# HLib-SPIDevices.net
KiCad netlist of a schematic drawn in Altium Designer
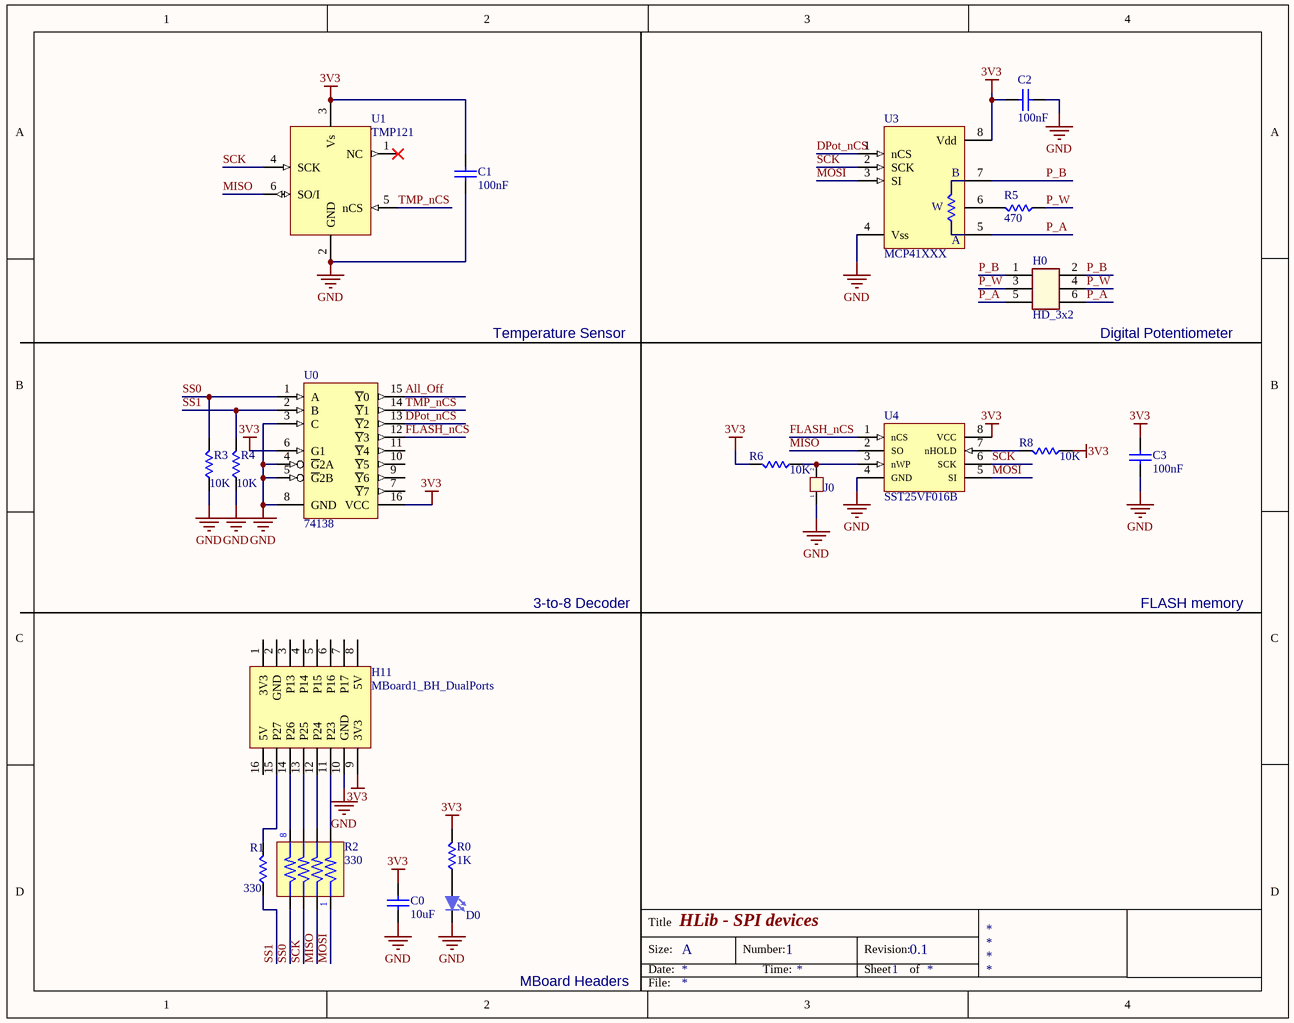
[diagram p0: HLib-SPIDevices.SchDoc]

(export (version "E")
  (design (tool "Eeschema 10.0.6"))
  (components
    (comp (ref "C0")
      (value "10uF")
      (footprint "SM_0805_C_CERAMIC")
      (description "Non-polarity ceramic capacitor")
      (fields (field (name "Comment") "C_Ceramic") (field (name "PUBLISHER") "Altium Limited"))
      (libsource (lib "HLib_discrete_sch") (part "C_Ceramic"))
    )
    (comp (ref "C1")
      (value "100nF")
      (footprint "SM_0805_C_CERAMIC")
      (description "Non-polarity ceramic capacitor")
      (fields (field (name "Comment") "C_Ceramic") (field (name "PUBLISHER") "Altium Limited"))
      (libsource (lib "HLib_discrete_sch") (part "C_Ceramic"))
    )
    (comp (ref "C2")
      (value "100nF")
      (footprint "SM_0805_C_CERAMIC")
      (description "Non-polarity ceramic capacitor")
      (fields (field (name "Comment") "C_Ceramic") (field (name "PUBLISHER") "Altium Limited"))
      (libsource (lib "HLib_discrete_sch") (part "C_Ceramic"))
    )
    (comp (ref "C3")
      (value "100nF")
      (footprint "SM_0805_C_CERAMIC")
      (description "Non-polarity ceramic capacitor")
      (fields (field (name "Comment") "C_Ceramic") (field (name "PUBLISHER") "Altium Limited"))
      (libsource (lib "HLib_discrete_sch") (part "C_Ceramic"))
    )
    (comp (ref "D0")
      (value "LED")
      (footprint "SM_0805_LED")
      (fields (field (name "PUBLISHER") "Altium Limited"))
      (libsource (lib "HLib_discrete_sch") (part "LED"))
    )
    (comp (ref "H0")
      (value "HD_3x2")
      (footprint "HD_male_3x2_100mil_straight")
      (description "Header, 3-pins/row, double row,")
      (libsource (lib "HLib_connector_sch") (part "HD_3x2"))
    )
    (comp (ref "H11")
      (value "MBoard1_BH_DualPorts")
      (footprint "MBoard1_BH_DualPorts")
      (libsource (lib "Nhat_Lib") (part "MBoard1_BH_DualPorts"))
    )
    (comp (ref "J0")
      (value "Jumper 2")
      (footprint "HD_MALE_2_100mil_straight")
      (libsource (lib "VioletofSun") (part "JP 2"))
    )
    (comp (ref "R0")
      (value "1K")
      (footprint "SM_0805_R")
      (description "Resistor")
      (fields (field (name "Comment") "R") (field (name "PUBLISHER") "Altium Limited"))
      (libsource (lib "HLib_discrete_sch") (part "R"))
    )
    (comp (ref "R1")
      (value "330")
      (footprint "SM_0805_R")
      (description "Resistor")
      (fields (field (name "Comment") "R") (field (name "PUBLISHER") "Altium Limited"))
      (libsource (lib "HLib_discrete_sch") (part "R"))
    )
    (comp (ref "R2") (value "330") (footprint "RA4") (libsource (lib "Nhat_Lib") (part "RA4")))
    (comp (ref "R3")
      (value "10K")
      (footprint "SM_0805_R")
      (description "Resistor")
      (fields (field (name "Comment") "R") (field (name "PUBLISHER") "Altium Limited"))
      (libsource (lib "HLib_discrete_sch") (part "R"))
    )
    (comp (ref "R4")
      (value "10K")
      (footprint "SM_0805_R")
      (description "Resistor")
      (fields (field (name "Comment") "R") (field (name "PUBLISHER") "Altium Limited"))
      (libsource (lib "HLib_discrete_sch") (part "R"))
    )
    (comp (ref "R5")
      (value "470")
      (footprint "SM_0805_R")
      (description "Resistor")
      (fields (field (name "PUBLISHER") "Altium Limited"))
      (libsource (lib "HLib_discrete_sch") (part "R"))
    )
    (comp (ref "R6")
      (value "10K")
      (footprint "SM_0805_R")
      (description "Resistor")
      (fields (field (name "PUBLISHER") "Altium Limited"))
      (libsource (lib "HLib_discrete_sch") (part "R"))
    )
    (comp (ref "R8")
      (value "10K")
      (footprint "SM_0805_R")
      (description "Resistor")
      (fields (field (name "PUBLISHER") "Altium Limited"))
      (libsource (lib "HLib_discrete_sch") (part "R"))
    )
    (comp (ref "U0")
      (value "74138")
      (footprint "SO-16")
      (description "3 -to- 8 Decoder - Out Low")
      (fields (field (name "COPYRIGHT BY") "VanDungEvn@Gmail.com"))
      (libsource (lib "Nhat_Lib") (part "74138"))
    )
    (comp (ref "U1") (value "TMP121") (footprint "SC70-6") (libsource (lib "Nhat_Lib") (part "TMP121")))
    (comp (ref "U3") (value "MCP41XXX") (footprint "SO-8") (libsource (lib "Nhat_Lib") (part "MCP41XXX")))
    (comp (ref "U4")
      (value "SST25VF016B")
      (footprint "SO-8")
      (libsource (lib "Nhat_Lib") (part "SST25VF016B"))
    )
  )
  (nets
    (net (code "1") (name "/All_Off") (class "Default")
      (node (ref "U0") (pin "15") (pinfunction "~{Y}0_15") (pintype "output"))
    )
    (net (code "2") (name "/DPot_nCS") (class "Default")
      (node (ref "U0") (pin "13") (pinfunction "~{Y}2_13") (pintype "output"))
      (node (ref "U3") (pin "1") (pinfunction "nCS_1") (pintype "input"))
    )
    (net (code "3") (name "/FLASH_nCS") (class "Default")
      (node (ref "U0") (pin "12") (pinfunction "~{Y}3_12") (pintype "output"))
      (node (ref "U4") (pin "1") (pinfunction "nCS_1") (pintype "input"))
    )
    (net (code "4") (name "/MISO") (class "Default")
      (node (ref "R2") (pin "3") (pinfunction "3_3") (pintype "passive"))
      (node (ref "U1") (pin "6") (pinfunction "SO/I_6") (pintype "bidirectional"))
      (node (ref "U4") (pin "2") (pinfunction "SO_2") (pintype "passive"))
    )
    (net (code "5") (name "/MOSI") (class "Default")
      (node (ref "R2") (pin "1") (pinfunction "1_1") (pintype "passive"))
      (node (ref "U3") (pin "3") (pinfunction "SI_3") (pintype "input"))
      (node (ref "U4") (pin "5") (pinfunction "SI_5") (pintype "passive"))
    )
    (net (code "6") (name "/P_A") (class "Default")
      (node (ref "H0") (pin "5") (pinfunction "5_5") (pintype "passive"))
      (node (ref "H0") (pin "6") (pinfunction "6_6") (pintype "passive"))
      (node (ref "U3") (pin "5") (pinfunction "PA0_5") (pintype "passive"))
    )
    (net (code "7") (name "/P_B") (class "Default")
      (node (ref "H0") (pin "1") (pinfunction "1_1") (pintype "passive"))
      (node (ref "H0") (pin "2") (pinfunction "2_2") (pintype "passive"))
      (node (ref "U3") (pin "7") (pinfunction "PB0_7") (pintype "passive"))
    )
    (net (code "8") (name "/P_W") (class "Default")
      (node (ref "H0") (pin "3") (pinfunction "3_3") (pintype "passive"))
      (node (ref "H0") (pin "4") (pinfunction "4_4") (pintype "passive"))
      (node (ref "R5") (pin "1") (pinfunction "1_1") (pintype "passive"))
    )
    (net (code "9") (name "/SCK") (class "Default")
      (node (ref "R2") (pin "5") (pinfunction "5_5") (pintype "passive"))
      (node (ref "U1") (pin "4") (pinfunction "SCK_4") (pintype "input"))
      (node (ref "U3") (pin "2") (pinfunction "SCK_2") (pintype "input"))
      (node (ref "U4") (pin "6") (pinfunction "SCK_6") (pintype "passive"))
    )
    (net (code "10") (name "/SS0") (class "Default")
      (node (ref "R2") (pin "7") (pinfunction "7_7") (pintype "passive"))
      (node (ref "R3") (pin "2") (pinfunction "2_2") (pintype "passive"))
      (node (ref "U0") (pin "1") (pinfunction "A_1") (pintype "input"))
    )
    (net (code "11") (name "/SS1") (class "Default")
      (node (ref "R1") (pin "1") (pinfunction "1_1") (pintype "passive"))
      (node (ref "R4") (pin "2") (pinfunction "2_2") (pintype "passive"))
      (node (ref "U0") (pin "2") (pinfunction "B_2") (pintype "input"))
    )
    (net (code "12") (name "/TMP_nCS") (class "Default")
      (node (ref "U0") (pin "14") (pinfunction "~{Y}1_14") (pintype "output"))
      (node (ref "U1") (pin "5") (pinfunction "nCS_5") (pintype "input"))
    )
    (net (code "13") (name "3V3") (class "Default")
      (node (ref "C0") (pin "2") (pinfunction "2_2") (pintype "passive"))
      (node (ref "C1") (pin "2") (pinfunction "2_2") (pintype "passive"))
      (node (ref "C2") (pin "2") (pinfunction "2_2") (pintype "passive"))
      (node (ref "C3") (pin "1") (pinfunction "1_1") (pintype "passive"))
      (node (ref "H11") (pin "9") (pinfunction "3V3_9") (pintype "passive"))
      (node (ref "R0") (pin "2") (pinfunction "2_2") (pintype "passive"))
      (node (ref "R6") (pin "2") (pinfunction "2_2") (pintype "passive"))
      (node (ref "R8") (pin "1") (pinfunction "1_1") (pintype "passive"))
      (node (ref "U0") (pin "16") (pinfunction "VCC_16") (pintype "passive"))
      (node (ref "U0") (pin "6") (pinfunction "G1_6") (pintype "input"))
      (node (ref "U1") (pin "3") (pinfunction "Vs_3") (pintype "power_in"))
      (node (ref "U3") (pin "8") (pinfunction "Vdd_8") (pintype "power_in"))
      (node (ref "U4") (pin "8") (pinfunction "VCC_8") (pintype "passive"))
    )
    (net (code "14") (name "GND") (class "Default")
      (node (ref "C0") (pin "1") (pinfunction "1_1") (pintype "passive"))
      (node (ref "C1") (pin "1") (pinfunction "1_1") (pintype "passive"))
      (node (ref "C2") (pin "1") (pinfunction "1_1") (pintype "passive"))
      (node (ref "C3") (pin "2") (pinfunction "2_2") (pintype "passive"))
      (node (ref "D0") (pin "2") (pinfunction "K_2") (pintype "passive"))
      (node (ref "H11") (pin "10") (pinfunction "GND_10") (pintype "passive"))
      (node (ref "J0") (pin "1") (pinfunction "1_1") (pintype "passive"))
      (node (ref "R3") (pin "1") (pinfunction "1_1") (pintype "passive"))
      (node (ref "R4") (pin "1") (pinfunction "1_1") (pintype "passive"))
      (node (ref "U0") (pin "3") (pinfunction "C_3") (pintype "input"))
      (node (ref "U0") (pin "4") (pinfunction "~{G}2A_4") (pintype "input"))
      (node (ref "U0") (pin "5") (pinfunction "~{G}2B_5") (pintype "input"))
      (node (ref "U0") (pin "8") (pinfunction "GND_8") (pintype "power_in"))
      (node (ref "U1") (pin "2") (pinfunction "GND_2") (pintype "power_in"))
      (node (ref "U3") (pin "4") (pinfunction "Vss_4") (pintype "power_in"))
      (node (ref "U4") (pin "4") (pinfunction "GND_4") (pintype "passive"))
    )
    (net (code "15") (name "Net-(D0-A)") (class "Default")
      (node (ref "D0") (pin "1") (pinfunction "A_1") (pintype "passive"))
      (node (ref "R0") (pin "1") (pinfunction "1_1") (pintype "passive"))
    )
    (net (code "16") (name "Net-(H11-P23)") (class "Default")
      (node (ref "H11") (pin "11") (pinfunction "P23_11") (pintype "passive"))
      (node (ref "R2") (pin "2") (pinfunction "2_2") (pintype "passive"))
    )
    (net (code "17") (name "Net-(H11-P24)") (class "Default")
      (node (ref "H11") (pin "12") (pinfunction "P24_12") (pintype "passive"))
      (node (ref "R2") (pin "4") (pinfunction "4_4") (pintype "passive"))
    )
    (net (code "18") (name "Net-(H11-P25)") (class "Default")
      (node (ref "H11") (pin "13") (pinfunction "P25_13") (pintype "passive"))
      (node (ref "R2") (pin "6") (pinfunction "6_6") (pintype "passive"))
    )
    (net (code "19") (name "Net-(H11-P26)") (class "Default")
      (node (ref "H11") (pin "14") (pinfunction "P26_14") (pintype "passive"))
      (node (ref "R2") (pin "8") (pinfunction "8_8") (pintype "passive"))
    )
    (net (code "20") (name "Net-(H11-P27)") (class "Default")
      (node (ref "H11") (pin "15") (pinfunction "P27_15") (pintype "passive"))
      (node (ref "R1") (pin "2") (pinfunction "2_2") (pintype "passive"))
    )
    (net (code "21") (name "Net-(U3-PW0)") (class "Default")
      (node (ref "R5") (pin "2") (pinfunction "2_2") (pintype "passive"))
      (node (ref "U3") (pin "6") (pinfunction "PW0_6") (pintype "passive"))
    )
    (net (code "22") (name "Net-(U4-nHOLD)") (class "Default")
      (node (ref "R8") (pin "2") (pinfunction "2_2") (pintype "passive"))
      (node (ref "U4") (pin "7") (pinfunction "nHOLD_7") (pintype "input"))
    )
    (net (code "23") (name "Net-(U4-nWP)") (class "Default")
      (node (ref "J0") (pin "2") (pinfunction "2_2") (pintype "passive"))
      (node (ref "R6") (pin "1") (pinfunction "1_1") (pintype "passive"))
      (node (ref "U4") (pin "3") (pinfunction "nWP_3") (pintype "input"))
    )
    (net (code "24") (name "unconnected-(H11-3V3-Pad1)") (class "Default")
      (node (ref "H11") (pin "1") (pinfunction "3V3_1") (pintype "passive"))
    )
    (net (code "25") (name "unconnected-(H11-5V-Pad8)") (class "Default")
      (node (ref "H11") (pin "8") (pinfunction "5V_8") (pintype "passive"))
    )
    (net (code "26") (name "unconnected-(H11-5V-Pad16)") (class "Default")
      (node (ref "H11") (pin "16") (pinfunction "5V_16") (pintype "passive"))
    )
    (net (code "27") (name "unconnected-(H11-GND-Pad2)") (class "Default")
      (node (ref "H11") (pin "2") (pinfunction "GND_2") (pintype "passive"))
    )
    (net (code "28") (name "unconnected-(H11-P13-Pad3)") (class "Default")
      (node (ref "H11") (pin "3") (pinfunction "P13_3") (pintype "passive"))
    )
    (net (code "29") (name "unconnected-(H11-P14-Pad4)") (class "Default")
      (node (ref "H11") (pin "4") (pinfunction "P14_4") (pintype "passive"))
    )
    (net (code "30") (name "unconnected-(H11-P15-Pad5)") (class "Default")
      (node (ref "H11") (pin "5") (pinfunction "P15_5") (pintype "passive"))
    )
    (net (code "31") (name "unconnected-(H11-P16-Pad6)") (class "Default")
      (node (ref "H11") (pin "6") (pinfunction "P16_6") (pintype "passive"))
    )
    (net (code "32") (name "unconnected-(H11-P17-Pad7)") (class "Default")
      (node (ref "H11") (pin "7") (pinfunction "P17_7") (pintype "passive"))
    )
    (net (code "33") (name "unconnected-(U0-~{Y}4-Pad11)") (class "Default")
      (node (ref "U0") (pin "11") (pinfunction "~{Y}4_11") (pintype "output"))
    )
    (net (code "34") (name "unconnected-(U0-~{Y}5-Pad10)") (class "Default")
      (node (ref "U0") (pin "10") (pinfunction "~{Y}5_10") (pintype "output"))
    )
    (net (code "35") (name "unconnected-(U0-~{Y}6-Pad9)") (class "Default")
      (node (ref "U0") (pin "9") (pinfunction "~{Y}6_9") (pintype "output"))
    )
    (net (code "36") (name "unconnected-(U0-~{Y}7-Pad7)") (class "Default")
      (node (ref "U0") (pin "7") (pinfunction "~{Y}7_7") (pintype "output"))
    )
    (net (code "37") (name "unconnected-(U1-NC-Pad1)") (class "Default")
      (node (ref "U1") (pin "1") (pinfunction "NC_1") (pintype "output+no_connect"))
    )
  )
)
